# SAMD21E_Uno_Zero.net
KiCad netlist of a schematic drawn in EAGLE
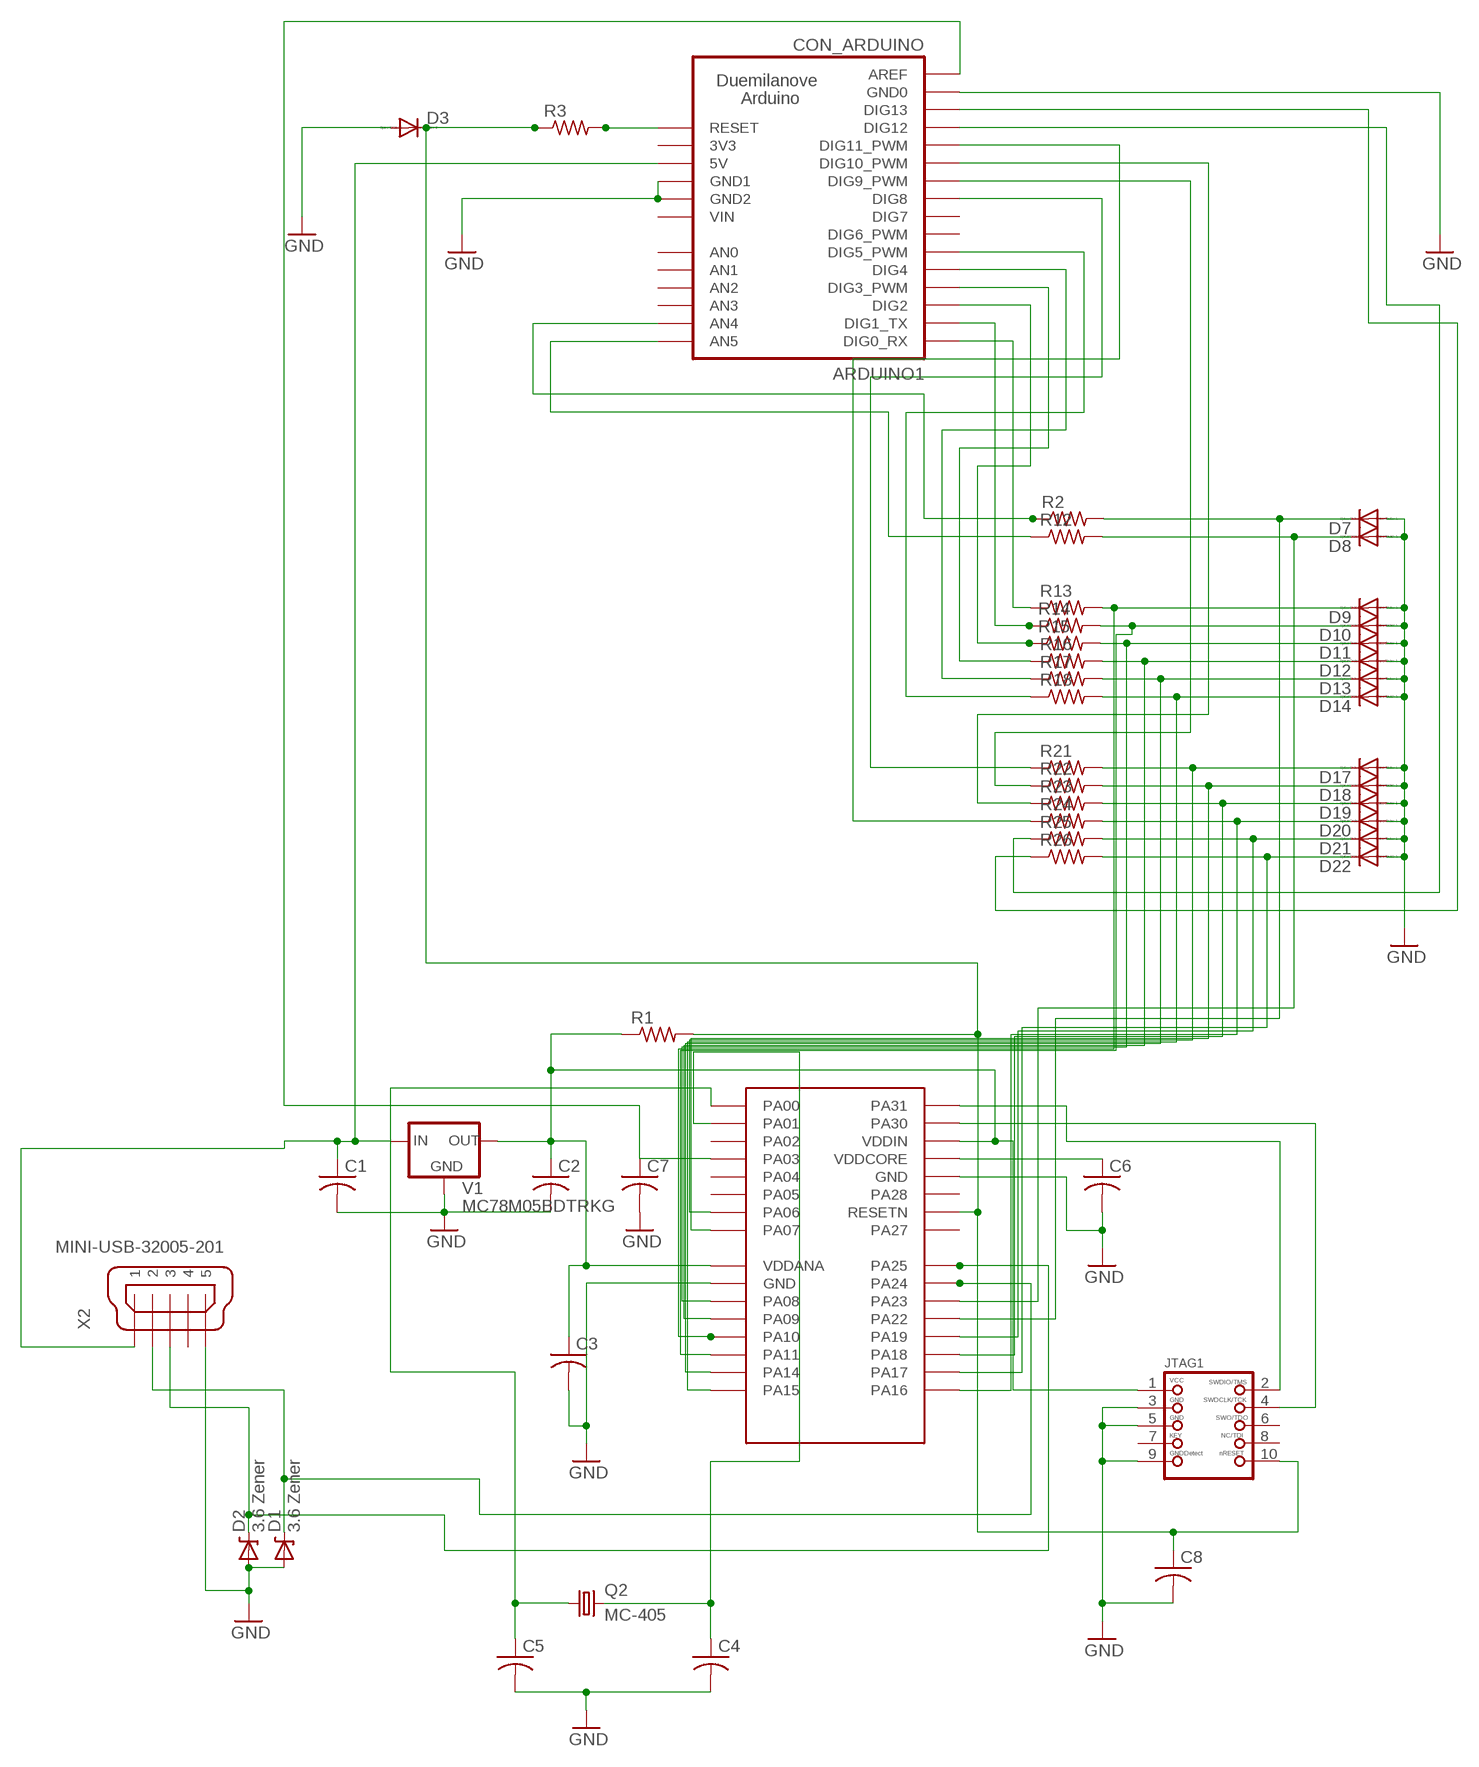
[diagram p0: schematic, sheet 1]

(export (version "E")
  (design (tool "Eeschema 10.0.6"))
  (components
    (comp (ref "ARDUINO1")
      (value "CON_ARDUINO")
      (footprint "eagle-import:CON_ARDUINO")
      (libsource (lib "eagle-import") (part "CON_ARDUINO"))
    )
    (comp (ref "C1")
      (value "C-USC0603K")
      (footprint "eagle-import:C0603K")
      (libsource (lib "eagle-import") (part "C-USC0603K"))
    )
    (comp (ref "C2")
      (value "C-USC0603K")
      (footprint "eagle-import:C0603K")
      (libsource (lib "eagle-import") (part "C-USC0603K"))
    )
    (comp (ref "C3")
      (value "C-USC0603")
      (footprint "eagle-import:C0603")
      (libsource (lib "eagle-import") (part "resistor_C-USC0603"))
    )
    (comp (ref "C4")
      (value "C-USC0603K")
      (footprint "eagle-import:C0603K")
      (libsource (lib "eagle-import") (part "resistor_C-USC0603K"))
    )
    (comp (ref "C5")
      (value "C-USC0603K")
      (footprint "eagle-import:C0603K")
      (libsource (lib "eagle-import") (part "resistor_C-USC0603K"))
    )
    (comp (ref "C6")
      (value "C-USC0603K")
      (footprint "eagle-import:C0603K")
      (libsource (lib "eagle-import") (part "C-USC0603K"))
    )
    (comp (ref "C7")
      (value "C-USC0603K")
      (footprint "eagle-import:C0603K")
      (libsource (lib "eagle-import") (part "C-USC0603K"))
    )
    (comp (ref "C8")
      (value "C-USC0603K")
      (footprint "eagle-import:C0603K")
      (libsource (lib "eagle-import") (part "C-USC0603K"))
    )
    (comp (ref "D1")
      (value "3.6 Zener")
      (footprint "eagle-import:SOD-323")
      (libsource (lib "eagle-import") (part "DIODE-ZENER-BZT52"))
    )
    (comp (ref "D2")
      (value "3.6 Zener")
      (footprint "eagle-import:SOD-323")
      (libsource (lib "eagle-import") (part "DIODE-ZENER-BZT52"))
    )
    (comp (ref "D3")
      (value "DIODE-SOD323-W")
      (footprint "eagle-import:SOD323-W")
      (libsource (lib "eagle-import") (part "DIODE-SOD323-W"))
    )
    (comp (ref "D7")
      (value "DIODE-SOD323-W")
      (footprint "eagle-import:SOD323-W")
      (libsource (lib "eagle-import") (part "DIODE-SOD323-W"))
    )
    (comp (ref "D8")
      (value "DIODE-SOD323-W")
      (footprint "eagle-import:SOD323-W")
      (libsource (lib "eagle-import") (part "DIODE-SOD323-W"))
    )
    (comp (ref "D9")
      (value "DIODE-SOD323-W")
      (footprint "eagle-import:SOD323-W")
      (libsource (lib "eagle-import") (part "DIODE-SOD323-W"))
    )
    (comp (ref "D10")
      (value "DIODE-SOD323-W")
      (footprint "eagle-import:SOD323-W")
      (libsource (lib "eagle-import") (part "DIODE-SOD323-W"))
    )
    (comp (ref "D11")
      (value "DIODE-SOD323-W")
      (footprint "eagle-import:SOD323-W")
      (libsource (lib "eagle-import") (part "DIODE-SOD323-W"))
    )
    (comp (ref "D12")
      (value "DIODE-SOD323-W")
      (footprint "eagle-import:SOD323-W")
      (libsource (lib "eagle-import") (part "DIODE-SOD323-W"))
    )
    (comp (ref "D13")
      (value "DIODE-SOD323-W")
      (footprint "eagle-import:SOD323-W")
      (libsource (lib "eagle-import") (part "DIODE-SOD323-W"))
    )
    (comp (ref "D14")
      (value "DIODE-SOD323-W")
      (footprint "eagle-import:SOD323-W")
      (libsource (lib "eagle-import") (part "DIODE-SOD323-W"))
    )
    (comp (ref "D17")
      (value "DIODE-SOD323-W")
      (footprint "eagle-import:SOD323-W")
      (libsource (lib "eagle-import") (part "DIODE-SOD323-W"))
    )
    (comp (ref "D18")
      (value "DIODE-SOD323-W")
      (footprint "eagle-import:SOD323-W")
      (libsource (lib "eagle-import") (part "DIODE-SOD323-W"))
    )
    (comp (ref "D19")
      (value "DIODE-SOD323-W")
      (footprint "eagle-import:SOD323-W")
      (libsource (lib "eagle-import") (part "DIODE-SOD323-W"))
    )
    (comp (ref "D20")
      (value "DIODE-SOD323-W")
      (footprint "eagle-import:SOD323-W")
      (libsource (lib "eagle-import") (part "DIODE-SOD323-W"))
    )
    (comp (ref "D21")
      (value "DIODE-SOD323-W")
      (footprint "eagle-import:SOD323-W")
      (libsource (lib "eagle-import") (part "DIODE-SOD323-W"))
    )
    (comp (ref "D22")
      (value "DIODE-SOD323-W")
      (footprint "eagle-import:SOD323-W")
      (libsource (lib "eagle-import") (part "DIODE-SOD323-W"))
    )
    (comp (ref "JTAG1")
      (value "JTAG-CORTEXM3")
      (footprint "eagle-import:2X05_1.27MM_SMT")
      (libsource (lib "eagle-import") (part "JTAG-CORTEXM3"))
    )
    (comp (ref "Q2")
      (value "MC-405")
      (footprint "eagle-import:MC-405")
      (libsource (lib "eagle-import") (part "MC-405"))
    )
    (comp (ref "R1")
      (value "R-US_R0603")
      (footprint "eagle-import:R0603")
      (libsource (lib "eagle-import") (part "R-US_R0603"))
    )
    (comp (ref "R2")
      (value "R-US_R0603")
      (footprint "eagle-import:R0603")
      (libsource (lib "eagle-import") (part "resistor_R-US_R0603"))
    )
    (comp (ref "R3")
      (value "R-US_R0603")
      (footprint "eagle-import:R0603")
      (libsource (lib "eagle-import") (part "resistor_R-US_R0603"))
    )
    (comp (ref "R12")
      (value "R-US_R0603")
      (footprint "eagle-import:R0603")
      (libsource (lib "eagle-import") (part "resistor_R-US_R0603"))
    )
    (comp (ref "R13")
      (value "R-US_R0603")
      (footprint "eagle-import:R0603")
      (libsource (lib "eagle-import") (part "resistor_R-US_R0603"))
    )
    (comp (ref "R14")
      (value "R-US_R0603")
      (footprint "eagle-import:R0603")
      (libsource (lib "eagle-import") (part "resistor_R-US_R0603"))
    )
    (comp (ref "R15")
      (value "R-US_R0603")
      (footprint "eagle-import:R0603")
      (libsource (lib "eagle-import") (part "resistor_R-US_R0603"))
    )
    (comp (ref "R16")
      (value "R-US_R0603")
      (footprint "eagle-import:R0603")
      (libsource (lib "eagle-import") (part "resistor_R-US_R0603"))
    )
    (comp (ref "R17")
      (value "R-US_R0603")
      (footprint "eagle-import:R0603")
      (libsource (lib "eagle-import") (part "resistor_R-US_R0603"))
    )
    (comp (ref "R18")
      (value "R-US_R0603")
      (footprint "eagle-import:R0603")
      (libsource (lib "eagle-import") (part "resistor_R-US_R0603"))
    )
    (comp (ref "R21")
      (value "R-US_R0603")
      (footprint "eagle-import:R0603")
      (libsource (lib "eagle-import") (part "resistor_R-US_R0603"))
    )
    (comp (ref "R22")
      (value "R-US_R0603")
      (footprint "eagle-import:R0603")
      (libsource (lib "eagle-import") (part "resistor_R-US_R0603"))
    )
    (comp (ref "R23")
      (value "R-US_R0603")
      (footprint "eagle-import:R0603")
      (libsource (lib "eagle-import") (part "resistor_R-US_R0603"))
    )
    (comp (ref "R24")
      (value "R-US_R0603")
      (footprint "eagle-import:R0603")
      (libsource (lib "eagle-import") (part "resistor_R-US_R0603"))
    )
    (comp (ref "R25")
      (value "R-US_R0603")
      (footprint "eagle-import:R0603")
      (libsource (lib "eagle-import") (part "resistor_R-US_R0603"))
    )
    (comp (ref "R26")
      (value "R-US_R0603")
      (footprint "eagle-import:R0603")
      (libsource (lib "eagle-import") (part "resistor_R-US_R0603"))
    )
    (comp (ref "U$8")
      (value "ATSAMD21E18A-AU")
      (footprint "eagle-import:32-TQFP")
      (libsource (lib "eagle-import") (part "ATSAMD21E18A-AU"))
    )
    (comp (ref "V1")
      (value "MC78M05BDTRKG")
      (footprint "eagle-import:DPACK")
      (libsource (lib "eagle-import") (part "LP2950?CDT-3.0"))
    )
    (comp (ref "X2")
      (value "MINI-USB-32005-201")
      (footprint "eagle-import:32005-201")
      (libsource (lib "eagle-import") (part "MINI-USB-32005-201"))
    )
  )
  (nets
    (net (code "1") (name "/VIN") (class "Default")
      (node (ref "ARDUINO1") (pin "VIN") (pinfunction "VIN_VIN") (pintype "power_in"))
    )
    (net (code "2") (name "GND") (class "Default")
      (node (ref "ARDUINO1") (pin "GND0") (pinfunction "GND0_GND0") (pintype "power_in"))
      (node (ref "ARDUINO1") (pin "GND1") (pinfunction "GND1_GND1") (pintype "power_in"))
      (node (ref "ARDUINO1") (pin "GND2") (pinfunction "GND2_GND2") (pintype "power_in"))
      (node (ref "C1") (pin "2") (pinfunction "2_2") (pintype "passive"))
      (node (ref "C2") (pin "2") (pinfunction "2_2") (pintype "passive"))
      (node (ref "C3") (pin "2") (pinfunction "2_2") (pintype "passive"))
      (node (ref "C4") (pin "2") (pinfunction "2_2") (pintype "passive"))
      (node (ref "C5") (pin "2") (pinfunction "2_2") (pintype "passive"))
      (node (ref "C6") (pin "2") (pinfunction "2_2") (pintype "passive"))
      (node (ref "C7") (pin "2") (pinfunction "2_2") (pintype "passive"))
      (node (ref "C8") (pin "2") (pinfunction "2_2") (pintype "passive"))
      (node (ref "D1") (pin "2") (pinfunction "A_2") (pintype "passive"))
      (node (ref "D10") (pin "A") (pinfunction "A_A") (pintype "passive"))
      (node (ref "D11") (pin "A") (pinfunction "A_A") (pintype "passive"))
      (node (ref "D12") (pin "A") (pinfunction "A_A") (pintype "passive"))
      (node (ref "D13") (pin "A") (pinfunction "A_A") (pintype "passive"))
      (node (ref "D14") (pin "A") (pinfunction "A_A") (pintype "passive"))
      (node (ref "D17") (pin "A") (pinfunction "A_A") (pintype "passive"))
      (node (ref "D18") (pin "A") (pinfunction "A_A") (pintype "passive"))
      (node (ref "D19") (pin "A") (pinfunction "A_A") (pintype "passive"))
      (node (ref "D2") (pin "2") (pinfunction "A_2") (pintype "passive"))
      (node (ref "D20") (pin "A") (pinfunction "A_A") (pintype "passive"))
      (node (ref "D21") (pin "A") (pinfunction "A_A") (pintype "passive"))
      (node (ref "D22") (pin "A") (pinfunction "A_A") (pintype "passive"))
      (node (ref "D3") (pin "A") (pinfunction "A_A") (pintype "passive"))
      (node (ref "D7") (pin "A") (pinfunction "A_A") (pintype "passive"))
      (node (ref "D8") (pin "A") (pinfunction "A_A") (pintype "passive"))
      (node (ref "D9") (pin "A") (pinfunction "A_A") (pintype "passive"))
      (node (ref "JTAG1") (pin "3") (pinfunction "3_3") (pintype "passive"))
      (node (ref "JTAG1") (pin "5") (pinfunction "5_5") (pintype "passive"))
      (node (ref "JTAG1") (pin "9") (pinfunction "9_9") (pintype "passive"))
      (node (ref "U$8") (pin "10") (pinfunction "GND_10") (pintype "bidirectional"))
      (node (ref "U$8") (pin "28") (pinfunction "GND_28") (pintype "bidirectional"))
      (node (ref "V1") (pin "4") (pinfunction "GND_4") (pintype "input"))
      (node (ref "X2") (pin "5") (pinfunction "5_5") (pintype "passive"))
    )
    (net (code "3") (name "Net-(ARDUINO1-AN4)") (class "Default")
      (node (ref "ARDUINO1") (pin "A_4") (pinfunction "AN4_A_4") (pintype "input"))
      (node (ref "R2") (pin "1") (pinfunction "1_1") (pintype "passive"))
    )
    (net (code "4") (name "Net-(ARDUINO1-AN5)") (class "Default")
      (node (ref "ARDUINO1") (pin "A_5") (pinfunction "AN5_A_5") (pintype "input"))
      (node (ref "R12") (pin "1") (pinfunction "1_1") (pintype "passive"))
    )
    (net (code "5") (name "Net-(ARDUINO1-DIG0_RX)") (class "Default")
      (node (ref "ARDUINO1") (pin "D_0") (pinfunction "DIG0_RX_D_0") (pintype "bidirectional"))
      (node (ref "R13") (pin "1") (pinfunction "1_1") (pintype "passive"))
    )
    (net (code "6") (name "Net-(ARDUINO1-DIG1_TX)") (class "Default")
      (node (ref "ARDUINO1") (pin "D_1") (pinfunction "DIG1_TX_D_1") (pintype "bidirectional"))
      (node (ref "R14") (pin "1") (pinfunction "1_1") (pintype "passive"))
    )
    (net (code "7") (name "Net-(ARDUINO1-DIG2)") (class "Default")
      (node (ref "ARDUINO1") (pin "D_2") (pinfunction "DIG2_D_2") (pintype "bidirectional"))
      (node (ref "R15") (pin "1") (pinfunction "1_1") (pintype "passive"))
    )
    (net (code "8") (name "Net-(ARDUINO1-DIG3_PWM)") (class "Default")
      (node (ref "ARDUINO1") (pin "D_3") (pinfunction "DIG3_PWM_D_3") (pintype "bidirectional"))
      (node (ref "R16") (pin "1") (pinfunction "1_1") (pintype "passive"))
    )
    (net (code "9") (name "Net-(ARDUINO1-DIG4)") (class "Default")
      (node (ref "ARDUINO1") (pin "D_4") (pinfunction "DIG4_D_4") (pintype "bidirectional"))
      (node (ref "R17") (pin "1") (pinfunction "1_1") (pintype "passive"))
    )
    (net (code "10") (name "Net-(ARDUINO1-DIG5_PWM)") (class "Default")
      (node (ref "ARDUINO1") (pin "D_5") (pinfunction "DIG5_PWM_D_5") (pintype "bidirectional"))
      (node (ref "R18") (pin "1") (pinfunction "1_1") (pintype "passive"))
    )
    (net (code "11") (name "Net-(ARDUINO1-DIG8)") (class "Default")
      (node (ref "ARDUINO1") (pin "D_8") (pinfunction "DIG8_D_8") (pintype "bidirectional"))
      (node (ref "R21") (pin "1") (pinfunction "1_1") (pintype "passive"))
    )
    (net (code "12") (name "Net-(ARDUINO1-DIG9_PWM)") (class "Default")
      (node (ref "ARDUINO1") (pin "D_9") (pinfunction "DIG9_PWM_D_9") (pintype "bidirectional"))
      (node (ref "R22") (pin "1") (pinfunction "1_1") (pintype "passive"))
    )
    (net (code "13") (name "Net-(ARDUINO1-DIG10_PWM)") (class "Default")
      (node (ref "ARDUINO1") (pin "D_10") (pinfunction "DIG10_PWM_D_10") (pintype "bidirectional"))
      (node (ref "R23") (pin "1") (pinfunction "1_1") (pintype "passive"))
    )
    (net (code "14") (name "Net-(ARDUINO1-DIG11_PWM)") (class "Default")
      (node (ref "ARDUINO1") (pin "D_11") (pinfunction "DIG11_PWM_D_11") (pintype "bidirectional"))
      (node (ref "R24") (pin "1") (pinfunction "1_1") (pintype "passive"))
    )
    (net (code "15") (name "Net-(ARDUINO1-DIG12)") (class "Default")
      (node (ref "ARDUINO1") (pin "D_12") (pinfunction "DIG12_D_12") (pintype "bidirectional"))
      (node (ref "R25") (pin "1") (pinfunction "1_1") (pintype "passive"))
    )
    (net (code "16") (name "Net-(ARDUINO1-DIG13)") (class "Default")
      (node (ref "ARDUINO1") (pin "D_13") (pinfunction "DIG13_D_13") (pintype "bidirectional"))
      (node (ref "R26") (pin "1") (pinfunction "1_1") (pintype "passive"))
    )
    (net (code "17") (name "Net-(ARDUINO1-PadRESET)") (class "Default")
      (node (ref "ARDUINO1") (pin "RESET") (pinfunction "RESET_RESET") (pintype "input"))
      (node (ref "R3") (pin "2") (pinfunction "2_2") (pintype "passive"))
    )
    (net (code "18") (name "Net-(D1-C)") (class "Default")
      (node (ref "D1") (pin "1") (pinfunction "C_1") (pintype "passive"))
      (node (ref "U$8") (pin "23") (pinfunction "PA24_23") (pintype "bidirectional"))
      (node (ref "X2") (pin "2") (pinfunction "2_2") (pintype "passive"))
    )
    (net (code "19") (name "Net-(D2-C)") (class "Default")
      (node (ref "D2") (pin "1") (pinfunction "C_1") (pintype "passive"))
      (node (ref "U$8") (pin "24") (pinfunction "PA25_24") (pintype "bidirectional"))
      (node (ref "X2") (pin "3") (pinfunction "3_3") (pintype "passive"))
    )
    (net (code "20") (name "Net-(U$8-PA00)") (class "Default")
      (node (ref "C5") (pin "1") (pinfunction "1_1") (pintype "passive"))
      (node (ref "Q2") (pin "1") (pinfunction "1_1") (pintype "passive"))
      (node (ref "U$8") (pin "1") (pinfunction "PA00_1") (pintype "bidirectional"))
    )
    (net (code "21") (name "Net-(U$8-PA01)") (class "Default")
      (node (ref "C4") (pin "1") (pinfunction "1_1") (pintype "passive"))
      (node (ref "Q2") (pin "2") (pinfunction "2_2") (pintype "passive"))
      (node (ref "U$8") (pin "2") (pinfunction "PA01_2") (pintype "bidirectional"))
    )
    (net (code "22") (name "Net-(U$8-PA03)") (class "Default")
      (node (ref "ARDUINO1") (pin "AREF") (pinfunction "AREF_AREF") (pintype "bidirectional"))
      (node (ref "C7") (pin "1") (pinfunction "1_1") (pintype "passive"))
      (node (ref "U$8") (pin "4") (pinfunction "PA03_4") (pintype "bidirectional"))
    )
    (net (code "23") (name "Net-(U$8-PA06)") (class "Default")
      (node (ref "D17") (pin "C") (pinfunction "C_C") (pintype "passive"))
      (node (ref "R21") (pin "2") (pinfunction "2_2") (pintype "passive"))
      (node (ref "U$8") (pin "7") (pinfunction "PA06_7") (pintype "bidirectional"))
    )
    (net (code "24") (name "Net-(U$8-PA07)") (class "Default")
      (node (ref "D18") (pin "C") (pinfunction "C_C") (pintype "passive"))
      (node (ref "R22") (pin "2") (pinfunction "2_2") (pintype "passive"))
      (node (ref "U$8") (pin "8") (pinfunction "PA07_8") (pintype "bidirectional"))
    )
    (net (code "25") (name "Net-(U$8-PA08)") (class "Default")
      (node (ref "D11") (pin "C") (pinfunction "C_C") (pintype "passive"))
      (node (ref "R15") (pin "2") (pinfunction "2_2") (pintype "passive"))
      (node (ref "U$8") (pin "11") (pinfunction "PA08_11") (pintype "bidirectional"))
    )
    (net (code "26") (name "Net-(U$8-PA09)") (class "Default")
      (node (ref "D12") (pin "C") (pinfunction "C_C") (pintype "passive"))
      (node (ref "R16") (pin "2") (pinfunction "2_2") (pintype "passive"))
      (node (ref "U$8") (pin "12") (pinfunction "PA09_12") (pintype "bidirectional"))
    )
    (net (code "27") (name "Net-(U$8-PA10)") (class "Default")
      (node (ref "D9") (pin "C") (pinfunction "C_C") (pintype "passive"))
      (node (ref "R13") (pin "2") (pinfunction "2_2") (pintype "passive"))
      (node (ref "U$8") (pin "13") (pinfunction "PA10_13") (pintype "bidirectional"))
    )
    (net (code "28") (name "Net-(U$8-PA11)") (class "Default")
      (node (ref "D10") (pin "C") (pinfunction "C_C") (pintype "passive"))
      (node (ref "R14") (pin "2") (pinfunction "2_2") (pintype "passive"))
      (node (ref "U$8") (pin "14") (pinfunction "PA11_14") (pintype "bidirectional"))
    )
    (net (code "29") (name "Net-(U$8-PA14)") (class "Default")
      (node (ref "D13") (pin "C") (pinfunction "C_C") (pintype "passive"))
      (node (ref "R17") (pin "2") (pinfunction "2_2") (pintype "passive"))
      (node (ref "U$8") (pin "15") (pinfunction "PA14_15") (pintype "bidirectional"))
    )
    (net (code "30") (name "Net-(U$8-PA15)") (class "Default")
      (node (ref "D14") (pin "C") (pinfunction "C_C") (pintype "passive"))
      (node (ref "R18") (pin "2") (pinfunction "2_2") (pintype "passive"))
      (node (ref "U$8") (pin "16") (pinfunction "PA15_16") (pintype "bidirectional"))
    )
    (net (code "31") (name "Net-(U$8-PA16)") (class "Default")
      (node (ref "D20") (pin "C") (pinfunction "C_C") (pintype "passive"))
      (node (ref "R24") (pin "2") (pinfunction "2_2") (pintype "passive"))
      (node (ref "U$8") (pin "17") (pinfunction "PA16_17") (pintype "bidirectional"))
    )
    (net (code "32") (name "Net-(U$8-PA17)") (class "Default")
      (node (ref "D22") (pin "C") (pinfunction "C_C") (pintype "passive"))
      (node (ref "R26") (pin "2") (pinfunction "2_2") (pintype "passive"))
      (node (ref "U$8") (pin "18") (pinfunction "PA17_18") (pintype "bidirectional"))
    )
    (net (code "33") (name "Net-(U$8-PA18)") (class "Default")
      (node (ref "D19") (pin "C") (pinfunction "C_C") (pintype "passive"))
      (node (ref "R23") (pin "2") (pinfunction "2_2") (pintype "passive"))
      (node (ref "U$8") (pin "19") (pinfunction "PA18_19") (pintype "bidirectional"))
    )
    (net (code "34") (name "Net-(U$8-PA19)") (class "Default")
      (node (ref "D21") (pin "C") (pinfunction "C_C") (pintype "passive"))
      (node (ref "R25") (pin "2") (pinfunction "2_2") (pintype "passive"))
      (node (ref "U$8") (pin "20") (pinfunction "PA19_20") (pintype "bidirectional"))
    )
    (net (code "35") (name "Net-(U$8-PA22)") (class "Default")
      (node (ref "D7") (pin "C") (pinfunction "C_C") (pintype "passive"))
      (node (ref "R2") (pin "2") (pinfunction "2_2") (pintype "passive"))
      (node (ref "U$8") (pin "21") (pinfunction "PA22_21") (pintype "bidirectional"))
    )
    (net (code "36") (name "Net-(U$8-PA23)") (class "Default")
      (node (ref "D8") (pin "C") (pinfunction "C_C") (pintype "passive"))
      (node (ref "R12") (pin "2") (pinfunction "2_2") (pintype "passive"))
      (node (ref "U$8") (pin "22") (pinfunction "PA23_22") (pintype "bidirectional"))
    )
    (net (code "37") (name "Net-(U$8-PA30)") (class "Default")
      (node (ref "JTAG1") (pin "4") (pinfunction "4_4") (pintype "passive"))
      (node (ref "U$8") (pin "31") (pinfunction "PA30_31") (pintype "bidirectional"))
    )
    (net (code "38") (name "Net-(U$8-PA31)") (class "Default")
      (node (ref "JTAG1") (pin "2") (pinfunction "2_2") (pintype "passive"))
      (node (ref "U$8") (pin "32") (pinfunction "PA31_32") (pintype "bidirectional"))
    )
    (net (code "39") (name "Net-(U$8-RESETN)") (class "Default")
      (node (ref "C8") (pin "1") (pinfunction "1_1") (pintype "passive"))
      (node (ref "D3") (pin "C") (pinfunction "C_C") (pintype "passive"))
      (node (ref "JTAG1") (pin "10") (pinfunction "10_10") (pintype "passive"))
      (node (ref "R1") (pin "2") (pinfunction "2_2") (pintype "passive"))
      (node (ref "R3") (pin "1") (pinfunction "1_1") (pintype "passive"))
      (node (ref "U$8") (pin "26") (pinfunction "RESETN_26") (pintype "bidirectional"))
    )
    (net (code "40") (name "Net-(U$8-VDDANA)") (class "Default")
      (node (ref "C2") (pin "1") (pinfunction "1_1") (pintype "passive"))
      (node (ref "C3") (pin "1") (pinfunction "1_1") (pintype "passive"))
      (node (ref "JTAG1") (pin "1") (pinfunction "1_1") (pintype "passive"))
      (node (ref "R1") (pin "1") (pinfunction "1_1") (pintype "passive"))
      (node (ref "U$8") (pin "30") (pinfunction "VDDIN_30") (pintype "bidirectional"))
      (node (ref "U$8") (pin "9") (pinfunction "VDDANA_9") (pintype "bidirectional"))
      (node (ref "V1") (pin "3") (pinfunction "OUT_3") (pintype "passive"))
    )
    (net (code "41") (name "Net-(U$8-VDDCORE)") (class "Default")
      (node (ref "C6") (pin "1") (pinfunction "1_1") (pintype "passive"))
      (node (ref "U$8") (pin "29") (pinfunction "VDDCORE_29") (pintype "bidirectional"))
    )
    (net (code "42") (name "Net-(V1-IN)") (class "Default")
      (node (ref "ARDUINO1") (pin "5V") (pinfunction "5V_5V") (pintype "bidirectional"))
      (node (ref "C1") (pin "1") (pinfunction "1_1") (pintype "passive"))
      (node (ref "V1") (pin "1") (pinfunction "IN_1") (pintype "input"))
      (node (ref "X2") (pin "1") (pinfunction "1_1") (pintype "passive"))
    )
    (net (code "43") (name "unconnected-(ARDUINO1-AN0-PadA_0)") (class "Default")
      (node (ref "ARDUINO1") (pin "A_0") (pinfunction "AN0_A_0") (pintype "input"))
    )
    (net (code "44") (name "unconnected-(ARDUINO1-AN1-PadA_1)") (class "Default")
      (node (ref "ARDUINO1") (pin "A_1") (pinfunction "AN1_A_1") (pintype "input"))
    )
    (net (code "45") (name "unconnected-(ARDUINO1-AN2-PadA_2)") (class "Default")
      (node (ref "ARDUINO1") (pin "A_2") (pinfunction "AN2_A_2") (pintype "input"))
    )
    (net (code "46") (name "unconnected-(ARDUINO1-AN3-PadA_3)") (class "Default")
      (node (ref "ARDUINO1") (pin "A_3") (pinfunction "AN3_A_3") (pintype "input"))
    )
    (net (code "47") (name "unconnected-(ARDUINO1-DIG6_PWM-PadD_6)") (class "Default")
      (node (ref "ARDUINO1") (pin "D_6") (pinfunction "DIG6_PWM_D_6") (pintype "bidirectional"))
    )
    (net (code "48") (name "unconnected-(ARDUINO1-DIG7-PadD_7)") (class "Default")
      (node (ref "ARDUINO1") (pin "D_7") (pinfunction "DIG7_D_7") (pintype "bidirectional"))
    )
    (net (code "49") (name "unconnected-(ARDUINO1-Pad3V3)") (class "Default")
      (node (ref "ARDUINO1") (pin "3V3") (pinfunction "3V3_3V3") (pintype "bidirectional"))
    )
    (net (code "50") (name "unconnected-(JTAG1-Pad6)") (class "Default")
      (node (ref "JTAG1") (pin "6") (pinfunction "6_6") (pintype "passive"))
    )
    (net (code "51") (name "unconnected-(JTAG1-Pad7)") (class "Default")
      (node (ref "JTAG1") (pin "7") (pinfunction "7_7") (pintype "passive"))
    )
    (net (code "52") (name "unconnected-(JTAG1-Pad8)") (class "Default")
      (node (ref "JTAG1") (pin "8") (pinfunction "8_8") (pintype "passive"))
    )
    (net (code "53") (name "unconnected-(U$8-PA02-Pad3)") (class "Default")
      (node (ref "U$8") (pin "3") (pinfunction "PA02_3") (pintype "bidirectional"))
    )
    (net (code "54") (name "unconnected-(U$8-PA04-Pad5)") (class "Default")
      (node (ref "U$8") (pin "5") (pinfunction "PA04_5") (pintype "bidirectional"))
    )
    (net (code "55") (name "unconnected-(U$8-PA05-Pad6)") (class "Default")
      (node (ref "U$8") (pin "6") (pinfunction "PA05_6") (pintype "bidirectional"))
    )
    (net (code "56") (name "unconnected-(U$8-PA27-Pad25)") (class "Default")
      (node (ref "U$8") (pin "25") (pinfunction "PA27_25") (pintype "bidirectional"))
    )
    (net (code "57") (name "unconnected-(U$8-PA28-Pad27)") (class "Default")
      (node (ref "U$8") (pin "27") (pinfunction "PA28_27") (pintype "bidirectional"))
    )
    (net (code "58") (name "unconnected-(X2-Pad4)") (class "Default")
      (node (ref "X2") (pin "4") (pinfunction "4_4") (pintype "passive"))
    )
  )
)
